# Aux_Power_Board_V2_1.net
KiCad netlist of a schematic drawn in EAGLE
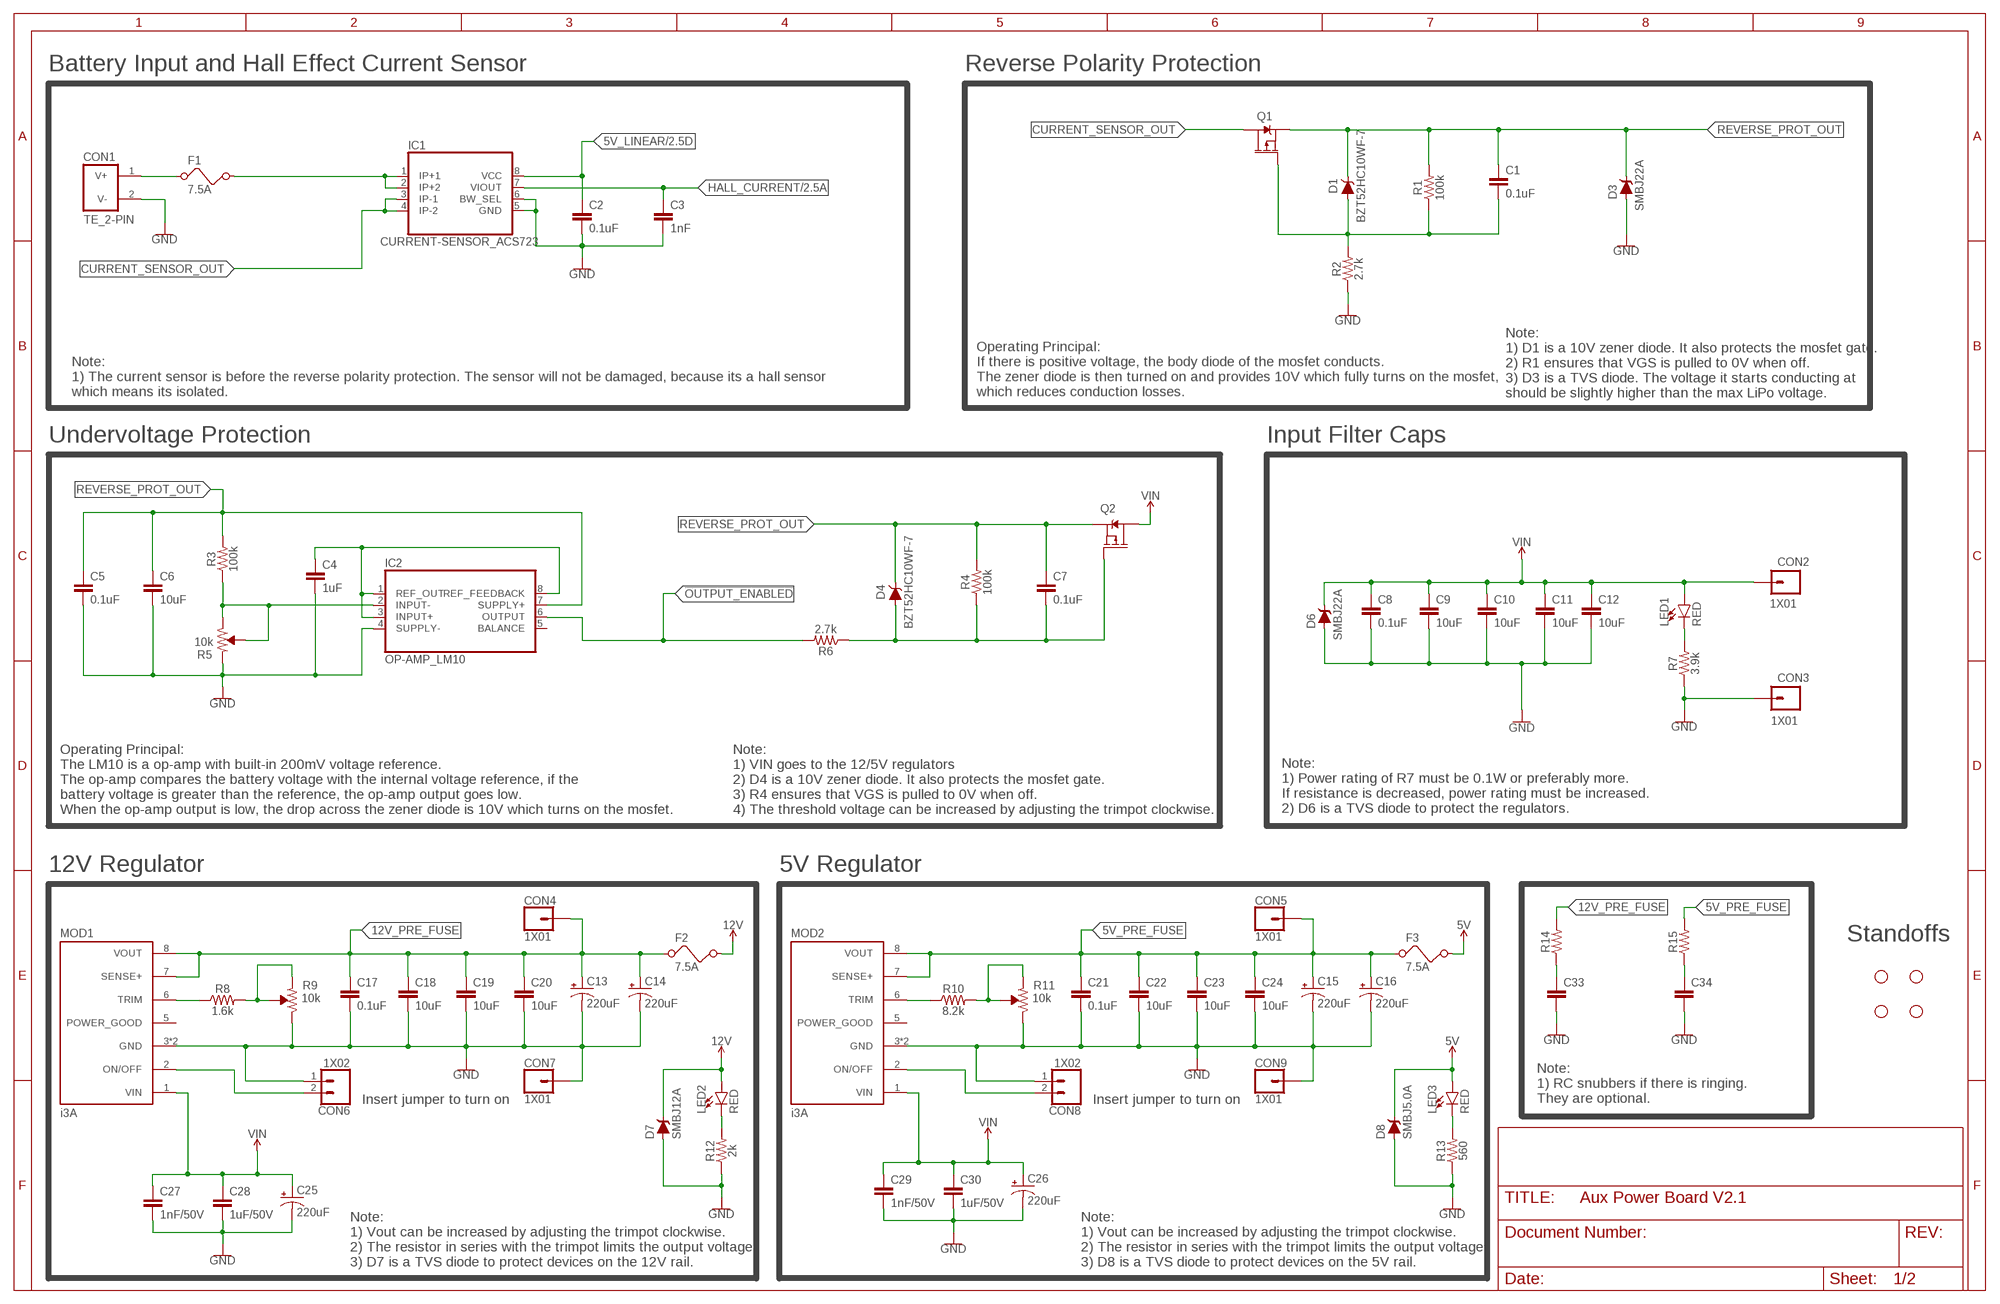
[diagram p0: schematic, sheet 1]
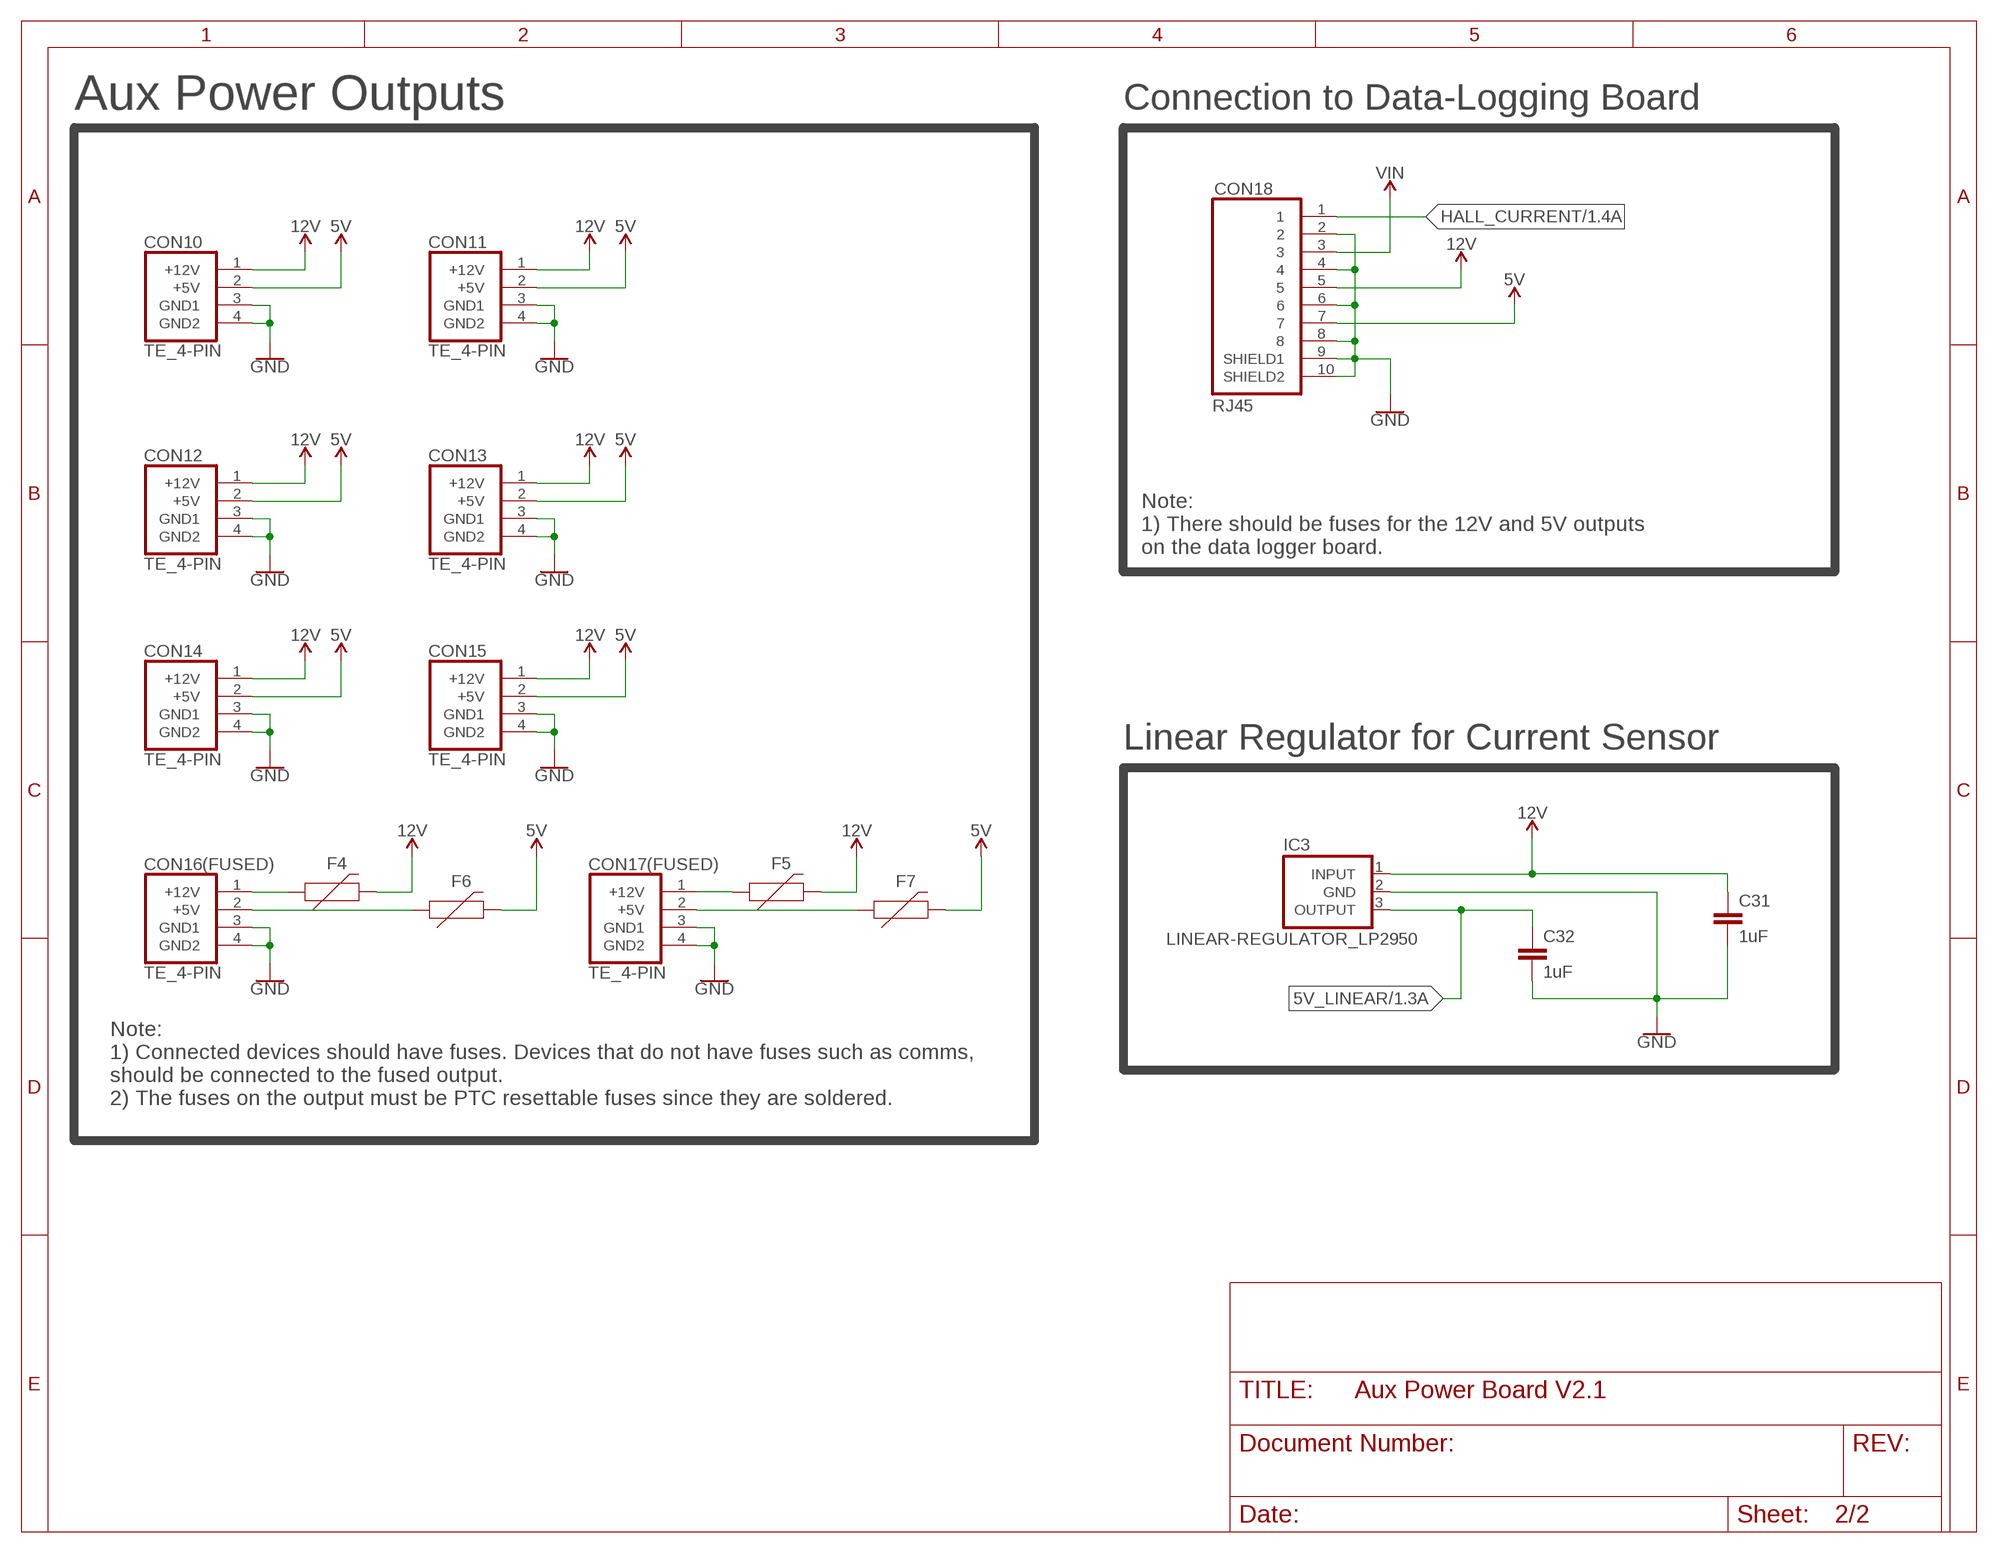
[diagram p1: schematic, sheet 2]

(export (version "E")
  (design (tool "Eeschema 10.0.6"))
  (components
    (comp (ref "C1")
      (value "0.1uF")
      (footprint "eagle-import:0805")
      (libsource (lib "eagle-import") (part "CAPACITOR_0805"))
    )
    (comp (ref "C2")
      (value "0.1uF")
      (footprint "eagle-import:0805")
      (libsource (lib "eagle-import") (part "CAPACITOR_0805"))
    )
    (comp (ref "C3")
      (value "1nF")
      (footprint "eagle-import:0805")
      (libsource (lib "eagle-import") (part "CAPACITOR_0805"))
    )
    (comp (ref "C4")
      (value "1uF")
      (footprint "eagle-import:0805")
      (libsource (lib "eagle-import") (part "CAPACITOR_0805"))
    )
    (comp (ref "C5")
      (value "0.1uF")
      (footprint "eagle-import:0805")
      (libsource (lib "eagle-import") (part "CAPACITOR_0805"))
    )
    (comp (ref "C6")
      (value "10uF")
      (footprint "eagle-import:1210")
      (libsource (lib "eagle-import") (part "CAPACITOR_1210"))
    )
    (comp (ref "C7")
      (value "0.1uF")
      (footprint "eagle-import:0805")
      (libsource (lib "eagle-import") (part "CAPACITOR_0805"))
    )
    (comp (ref "C8")
      (value "0.1uF")
      (footprint "eagle-import:0805")
      (libsource (lib "eagle-import") (part "CAPACITOR_0805"))
    )
    (comp (ref "C9")
      (value "10uF")
      (footprint "eagle-import:1210")
      (libsource (lib "eagle-import") (part "CAPACITOR_1210"))
    )
    (comp (ref "C10")
      (value "10uF")
      (footprint "eagle-import:1210")
      (libsource (lib "eagle-import") (part "CAPACITOR_1210"))
    )
    (comp (ref "C11")
      (value "10uF")
      (footprint "eagle-import:1210")
      (libsource (lib "eagle-import") (part "CAPACITOR_1210"))
    )
    (comp (ref "C12")
      (value "10uF")
      (footprint "eagle-import:1210")
      (libsource (lib "eagle-import") (part "CAPACITOR_1210"))
    )
    (comp (ref "C13")
      (value "220uF")
      (footprint "eagle-import:CAPACITOR_220UF_63V")
      (libsource (lib "eagle-import") (part "CAPACITOR_ELECTROLYTIC_220UF"))
    )
    (comp (ref "C14")
      (value "220uF")
      (footprint "eagle-import:CAPACITOR_220UF_63V")
      (libsource (lib "eagle-import") (part "CAPACITOR_ELECTROLYTIC_220UF"))
    )
    (comp (ref "C15")
      (value "220uF")
      (footprint "eagle-import:CAPACITOR_220UF_63V")
      (libsource (lib "eagle-import") (part "CAPACITOR_ELECTROLYTIC_220UF"))
    )
    (comp (ref "C16")
      (value "220uF")
      (footprint "eagle-import:CAPACITOR_220UF_63V")
      (libsource (lib "eagle-import") (part "CAPACITOR_ELECTROLYTIC_220UF"))
    )
    (comp (ref "C17")
      (value "0.1uF")
      (footprint "eagle-import:0805")
      (libsource (lib "eagle-import") (part "CAPACITOR_0805"))
    )
    (comp (ref "C18")
      (value "10uF")
      (footprint "eagle-import:0805")
      (libsource (lib "eagle-import") (part "CAPACITOR_0805"))
    )
    (comp (ref "C19")
      (value "10uF")
      (footprint "eagle-import:0805")
      (libsource (lib "eagle-import") (part "CAPACITOR_0805"))
    )
    (comp (ref "C20")
      (value "10uF")
      (footprint "eagle-import:0805")
      (libsource (lib "eagle-import") (part "CAPACITOR_0805"))
    )
    (comp (ref "C21")
      (value "0.1uF")
      (footprint "eagle-import:0805")
      (libsource (lib "eagle-import") (part "CAPACITOR_0805"))
    )
    (comp (ref "C22")
      (value "10uF")
      (footprint "eagle-import:0805")
      (libsource (lib "eagle-import") (part "CAPACITOR_0805"))
    )
    (comp (ref "C23")
      (value "10uF")
      (footprint "eagle-import:0805")
      (libsource (lib "eagle-import") (part "CAPACITOR_0805"))
    )
    (comp (ref "C24")
      (value "10uF")
      (footprint "eagle-import:0805")
      (libsource (lib "eagle-import") (part "CAPACITOR_0805"))
    )
    (comp (ref "C25")
      (value "220uF")
      (footprint "eagle-import:CAPACITOR_220UF_63V")
      (libsource (lib "eagle-import") (part "CAPACITOR_ELECTROLYTIC_220UF"))
    )
    (comp (ref "C26")
      (value "220uF")
      (footprint "eagle-import:CAPACITOR_220UF_63V")
      (libsource (lib "eagle-import") (part "CAPACITOR_ELECTROLYTIC_220UF"))
    )
    (comp (ref "C27")
      (value "1nF/50V")
      (footprint "eagle-import:0805")
      (libsource (lib "eagle-import") (part "CAPACITOR_0805"))
    )
    (comp (ref "C28")
      (value "1uF/50V")
      (footprint "eagle-import:0805")
      (libsource (lib "eagle-import") (part "CAPACITOR_0805"))
    )
    (comp (ref "C29")
      (value "1nF/50V")
      (footprint "eagle-import:0805")
      (libsource (lib "eagle-import") (part "CAPACITOR_0805"))
    )
    (comp (ref "C30")
      (value "1uF/50V")
      (footprint "eagle-import:0805")
      (libsource (lib "eagle-import") (part "CAPACITOR_0805"))
    )
    (comp (ref "C33")
      (value "CAPACITOR_0805")
      (footprint "eagle-import:0805")
      (libsource (lib "eagle-import") (part "CAPACITOR_0805"))
    )
    (comp (ref "C34")
      (value "CAPACITOR_0805")
      (footprint "eagle-import:0805")
      (libsource (lib "eagle-import") (part "CAPACITOR_0805"))
    )
    (comp (ref "CON1")
      (value "TE_2-PIN")
      (footprint "eagle-import:TE_2-PIN")
      (libsource (lib "eagle-import") (part "TE_2-PIN"))
    )
    (comp (ref "CON2")
      (value "1X01")
      (footprint "eagle-import:1X01")
      (libsource (lib "eagle-import") (part "1X01"))
    )
    (comp (ref "CON3")
      (value "1X01")
      (footprint "eagle-import:1X01")
      (libsource (lib "eagle-import") (part "1X01"))
    )
    (comp (ref "CON4")
      (value "1X01")
      (footprint "eagle-import:1X01")
      (libsource (lib "eagle-import") (part "1X01"))
    )
    (comp (ref "CON5")
      (value "1X01")
      (footprint "eagle-import:1X01")
      (libsource (lib "eagle-import") (part "1X01"))
    )
    (comp (ref "CON6")
      (value "1X02")
      (footprint "eagle-import:1X02")
      (libsource (lib "eagle-import") (part "1X02"))
    )
    (comp (ref "CON7")
      (value "1X01")
      (footprint "eagle-import:1X01")
      (libsource (lib "eagle-import") (part "1X01"))
    )
    (comp (ref "CON8")
      (value "1X02")
      (footprint "eagle-import:1X02")
      (libsource (lib "eagle-import") (part "1X02"))
    )
    (comp (ref "CON9")
      (value "1X01")
      (footprint "eagle-import:1X01")
      (libsource (lib "eagle-import") (part "1X01"))
    )
    (comp (ref "D1")
      (value "BZT52HC10WF-7")
      (footprint "eagle-import:SOD123FL")
      (libsource (lib "eagle-import") (part "DIODE_ZENER_SOD123F"))
    )
    (comp (ref "D3")
      (value "SMBJ22A")
      (footprint "eagle-import:DO214AA")
      (libsource (lib "eagle-import") (part "DIODE_TVS_UNI_DO-214AA"))
    )
    (comp (ref "D4")
      (value "BZT52HC10WF-7")
      (footprint "eagle-import:SOD123FL")
      (libsource (lib "eagle-import") (part "DIODE_ZENER_SOD123F"))
    )
    (comp (ref "D6")
      (value "SMBJ22A")
      (footprint "eagle-import:DO214AA")
      (libsource (lib "eagle-import") (part "DIODE_TVS_UNI_DO-214AA"))
    )
    (comp (ref "D7")
      (value "SMBJ12A")
      (footprint "eagle-import:DO214AA")
      (libsource (lib "eagle-import") (part "DIODE_TVS_UNI_DO-214AA"))
    )
    (comp (ref "D8")
      (value "SMBJ5.0A")
      (footprint "eagle-import:DO214AA")
      (libsource (lib "eagle-import") (part "DIODE_TVS_UNI_DO-214AA"))
    )
    (comp (ref "F1")
      (value "7.5A")
      (footprint "eagle-import:FUSEHOLDER_VERTICAL")
      (libsource (lib "eagle-import") (part "FUSEHOLDER_VERTICAL"))
    )
    (comp (ref "F2")
      (value "7.5A")
      (footprint "eagle-import:FUSEHOLDER_VERTICAL")
      (libsource (lib "eagle-import") (part "FUSEHOLDER_VERTICAL"))
    )
    (comp (ref "F3")
      (value "7.5A")
      (footprint "eagle-import:FUSEHOLDER_VERTICAL")
      (libsource (lib "eagle-import") (part "FUSEHOLDER_VERTICAL"))
    )
    (comp (ref "H1")
      (value "STAND-OFF")
      (footprint "eagle-import:STAND-OFF")
      (libsource (lib "eagle-import") (part "STAND-OFF"))
    )
    (comp (ref "H2")
      (value "STAND-OFF")
      (footprint "eagle-import:STAND-OFF")
      (libsource (lib "eagle-import") (part "STAND-OFF"))
    )
    (comp (ref "H3")
      (value "STAND-OFF")
      (footprint "eagle-import:STAND-OFF")
      (libsource (lib "eagle-import") (part "STAND-OFF"))
    )
    (comp (ref "H4")
      (value "STAND-OFF")
      (footprint "eagle-import:STAND-OFF")
      (libsource (lib "eagle-import") (part "STAND-OFF"))
    )
    (comp (ref "IC1")
      (value "CURRENT-SENSOR_ACS723")
      (footprint "eagle-import:SOIC8")
      (libsource (lib "eagle-import") (part "CURRENT-SENSOR_ACS723"))
    )
    (comp (ref "IC2")
      (value "OP-AMP_LM10")
      (footprint "eagle-import:DIP08")
      (libsource (lib "eagle-import") (part "OP-AMP_LM10"))
    )
    (comp (ref "LED1")
      (value "RED")
      (footprint "eagle-import:0805_LED")
      (libsource (lib "eagle-import") (part "LED_0805"))
    )
    (comp (ref "LED2")
      (value "RED")
      (footprint "eagle-import:0805_LED")
      (libsource (lib "eagle-import") (part "LED_0805"))
    )
    (comp (ref "LED3")
      (value "RED")
      (footprint "eagle-import:0805_LED")
      (libsource (lib "eagle-import") (part "LED_0805"))
    )
    (comp (ref "MOD1")
      (value "i3A")
      (footprint "eagle-import:CONVERTER_I3A")
      (libsource (lib "eagle-import") (part "CONVERTER_I3A"))
    )
    (comp (ref "MOD2")
      (value "i3A")
      (footprint "eagle-import:CONVERTER_I3A")
      (libsource (lib "eagle-import") (part "CONVERTER_I3A"))
    )
    (comp (ref "Q1")
      (value "MOSFET_PMOS_TO-263")
      (footprint "eagle-import:TO-263_D2PAK")
      (libsource (lib "eagle-import") (part "MOSFET_PMOS_TO-263"))
    )
    (comp (ref "Q2")
      (value "MOSFET_PMOS_TO-263")
      (footprint "eagle-import:TO-263_D2PAK")
      (libsource (lib "eagle-import") (part "MOSFET_PMOS_TO-263"))
    )
    (comp (ref "R1")
      (value "100k")
      (footprint "eagle-import:0805")
      (libsource (lib "eagle-import") (part "RESISTOR_0805"))
    )
    (comp (ref "R2")
      (value "2.7k")
      (footprint "eagle-import:0805")
      (libsource (lib "eagle-import") (part "RESISTOR_0805"))
    )
    (comp (ref "R3")
      (value "100k")
      (footprint "eagle-import:0805")
      (libsource (lib "eagle-import") (part "RESISTOR_0805"))
    )
    (comp (ref "R4")
      (value "100k")
      (footprint "eagle-import:0805")
      (libsource (lib "eagle-import") (part "RESISTOR_0805"))
    )
    (comp (ref "R5")
      (value "10k")
      (footprint "eagle-import:TRIMPOT")
      (libsource (lib "eagle-import") (part "RESISTOR_TRIMPOT"))
    )
    (comp (ref "R6")
      (value "2.7k")
      (footprint "eagle-import:0805")
      (libsource (lib "eagle-import") (part "RESISTOR_0805"))
    )
    (comp (ref "R7")
      (value "3.9k")
      (footprint "eagle-import:0805")
      (libsource (lib "eagle-import") (part "RESISTOR_0805"))
    )
    (comp (ref "R8")
      (value "1.6k")
      (footprint "eagle-import:0805")
      (libsource (lib "eagle-import") (part "RESISTOR_0805"))
    )
    (comp (ref "R9")
      (value "10k")
      (footprint "eagle-import:TRIMPOT")
      (libsource (lib "eagle-import") (part "RESISTOR_TRIMPOT"))
    )
    (comp (ref "R10")
      (value "8.2k")
      (footprint "eagle-import:0805")
      (libsource (lib "eagle-import") (part "RESISTOR_0805"))
    )
    (comp (ref "R11")
      (value "10k")
      (footprint "eagle-import:TRIMPOT")
      (libsource (lib "eagle-import") (part "RESISTOR_TRIMPOT"))
    )
    (comp (ref "R12")
      (value "2k")
      (footprint "eagle-import:0805")
      (libsource (lib "eagle-import") (part "RESISTOR_0805"))
    )
    (comp (ref "R13")
      (value "560")
      (footprint "eagle-import:0805")
      (libsource (lib "eagle-import") (part "RESISTOR_0805"))
    )
    (comp (ref "R14")
      (value "RESISTOR_0805")
      (footprint "eagle-import:0805")
      (libsource (lib "eagle-import") (part "RESISTOR_0805"))
    )
    (comp (ref "R15")
      (value "RESISTOR_0805")
      (footprint "eagle-import:0805")
      (libsource (lib "eagle-import") (part "RESISTOR_0805"))
    )
    (comp (ref "C31")
      (value "1uF")
      (footprint "eagle-import:0805")
      (libsource (lib "eagle-import") (part "CAPACITOR_0805"))
    )
    (comp (ref "C32")
      (value "1uF")
      (footprint "eagle-import:0805")
      (libsource (lib "eagle-import") (part "CAPACITOR_0805"))
    )
    (comp (ref "CON10")
      (value "TE_4-PIN")
      (footprint "eagle-import:TE_4-PIN")
      (libsource (lib "eagle-import") (part "TE_4-PIN"))
    )
    (comp (ref "CON11")
      (value "TE_4-PIN")
      (footprint "eagle-import:TE_4-PIN")
      (libsource (lib "eagle-import") (part "TE_4-PIN"))
    )
    (comp (ref "CON12")
      (value "TE_4-PIN")
      (footprint "eagle-import:TE_4-PIN")
      (libsource (lib "eagle-import") (part "TE_4-PIN"))
    )
    (comp (ref "CON13")
      (value "TE_4-PIN")
      (footprint "eagle-import:TE_4-PIN")
      (libsource (lib "eagle-import") (part "TE_4-PIN"))
    )
    (comp (ref "CON14")
      (value "TE_4-PIN")
      (footprint "eagle-import:TE_4-PIN")
      (libsource (lib "eagle-import") (part "TE_4-PIN"))
    )
    (comp (ref "CON15")
      (value "TE_4-PIN")
      (footprint "eagle-import:TE_4-PIN")
      (libsource (lib "eagle-import") (part "TE_4-PIN"))
    )
    (comp (ref "CON16(FUSED)")
      (value "TE_4-PIN")
      (footprint "eagle-import:TE_4-PIN")
      (libsource (lib "eagle-import") (part "TE_4-PIN"))
    )
    (comp (ref "CON17(FUSED)")
      (value "TE_4-PIN")
      (footprint "eagle-import:TE_4-PIN")
      (libsource (lib "eagle-import") (part "TE_4-PIN"))
    )
    (comp (ref "CON18")
      (value "RJ45")
      (footprint "eagle-import:RJ45")
      (libsource (lib "eagle-import") (part "RJ45"))
    )
    (comp (ref "F4")
      (value "FUSE_1210_RESETTABLE")
      (footprint "eagle-import:1210")
      (libsource (lib "eagle-import") (part "FUSE_1210_RESETTABLE"))
    )
    (comp (ref "F5")
      (value "FUSE_1210_RESETTABLE")
      (footprint "eagle-import:1210")
      (libsource (lib "eagle-import") (part "FUSE_1210_RESETTABLE"))
    )
    (comp (ref "F6")
      (value "FUSE_1210_RESETTABLE")
      (footprint "eagle-import:1210")
      (libsource (lib "eagle-import") (part "FUSE_1210_RESETTABLE"))
    )
    (comp (ref "F7")
      (value "FUSE_1210_RESETTABLE")
      (footprint "eagle-import:1210")
      (libsource (lib "eagle-import") (part "FUSE_1210_RESETTABLE"))
    )
    (comp (ref "IC3")
      (value "LINEAR-REGULATOR_LP2950")
      (footprint "eagle-import:TO92")
      (libsource (lib "eagle-import") (part "LINEAR-REGULATOR_LP2950"))
    )
  )
  (nets
    (net (code "1") (name "5V") (class "Default")
      (node (ref "CON10") (pin "2") (pinfunction "+5V_2") (pintype "passive"))
      (node (ref "CON11") (pin "2") (pinfunction "+5V_2") (pintype "passive"))
      (node (ref "CON12") (pin "2") (pinfunction "+5V_2") (pintype "passive"))
      (node (ref "CON13") (pin "2") (pinfunction "+5V_2") (pintype "passive"))
      (node (ref "CON14") (pin "2") (pinfunction "+5V_2") (pintype "passive"))
      (node (ref "CON15") (pin "2") (pinfunction "+5V_2") (pintype "passive"))
      (node (ref "CON18") (pin "7") (pinfunction "7_7") (pintype "passive"))
      (node (ref "D8") (pin "C") (pinfunction "C_C") (pintype "passive"))
      (node (ref "F3") (pin "3") (pinfunction "2_3") (pintype "passive"))
      (node (ref "F3") (pin "4") (pinfunction "2_4") (pintype "passive"))
      (node (ref "F6") (pin "2") (pinfunction "2_2") (pintype "bidirectional"))
      (node (ref "F7") (pin "2") (pinfunction "2_2") (pintype "bidirectional"))
      (node (ref "LED3") (pin "1") (pinfunction "A_1") (pintype "passive"))
    )
    (net (code "2") (name "5V_LINEAR") (class "Default")
      (node (ref "C2") (pin "1") (pinfunction "1_1") (pintype "passive"))
      (node (ref "C32") (pin "1") (pinfunction "1_1") (pintype "passive"))
      (node (ref "IC1") (pin "8") (pinfunction "VCC_8") (pintype "bidirectional"))
      (node (ref "IC3") (pin "3") (pinfunction "OUTPUT_3") (pintype "bidirectional"))
    )
    (net (code "3") (name "5V_PRE_FUSE") (class "Default")
      (node (ref "C15") (pin "+") (pinfunction "+_+") (pintype "passive"))
      (node (ref "C16") (pin "+") (pinfunction "+_+") (pintype "passive"))
      (node (ref "C21") (pin "1") (pinfunction "1_1") (pintype "passive"))
      (node (ref "C22") (pin "1") (pinfunction "1_1") (pintype "passive"))
      (node (ref "C23") (pin "1") (pinfunction "1_1") (pintype "passive"))
      (node (ref "C24") (pin "1") (pinfunction "1_1") (pintype "passive"))
      (node (ref "CON5") (pin "1") (pinfunction "1_1") (pintype "passive"))
      (node (ref "F3") (pin "1") (pinfunction "1_1") (pintype "passive"))
      (node (ref "F3") (pin "2") (pinfunction "1_2") (pintype "passive"))
      (node (ref "MOD2") (pin "7") (pinfunction "SENSE+_7") (pintype "bidirectional"))
      (node (ref "MOD2") (pin "8") (pinfunction "VOUT_8") (pintype "bidirectional"))
      (node (ref "R15") (pin "2") (pinfunction "2_2") (pintype "passive"))
    )
    (net (code "4") (name "12V") (class "Default")
      (node (ref "C31") (pin "1") (pinfunction "1_1") (pintype "passive"))
      (node (ref "CON10") (pin "1") (pinfunction "+12V_1") (pintype "passive"))
      (node (ref "CON11") (pin "1") (pinfunction "+12V_1") (pintype "passive"))
      (node (ref "CON12") (pin "1") (pinfunction "+12V_1") (pintype "passive"))
      (node (ref "CON13") (pin "1") (pinfunction "+12V_1") (pintype "passive"))
      (node (ref "CON14") (pin "1") (pinfunction "+12V_1") (pintype "passive"))
      (node (ref "CON15") (pin "1") (pinfunction "+12V_1") (pintype "passive"))
      (node (ref "CON18") (pin "5") (pinfunction "5_5") (pintype "passive"))
      (node (ref "D7") (pin "C") (pinfunction "C_C") (pintype "passive"))
      (node (ref "F2") (pin "3") (pinfunction "2_3") (pintype "passive"))
      (node (ref "F2") (pin "4") (pinfunction "2_4") (pintype "passive"))
      (node (ref "F4") (pin "2") (pinfunction "2_2") (pintype "bidirectional"))
      (node (ref "F5") (pin "2") (pinfunction "2_2") (pintype "bidirectional"))
      (node (ref "IC3") (pin "1") (pinfunction "INPUT_1") (pintype "bidirectional"))
      (node (ref "LED2") (pin "1") (pinfunction "A_1") (pintype "passive"))
    )
    (net (code "5") (name "12V_PRE_FUSE") (class "Default")
      (node (ref "C13") (pin "+") (pinfunction "+_+") (pintype "passive"))
      (node (ref "C14") (pin "+") (pinfunction "+_+") (pintype "passive"))
      (node (ref "C17") (pin "1") (pinfunction "1_1") (pintype "passive"))
      (node (ref "C18") (pin "1") (pinfunction "1_1") (pintype "passive"))
      (node (ref "C19") (pin "1") (pinfunction "1_1") (pintype "passive"))
      (node (ref "C20") (pin "1") (pinfunction "1_1") (pintype "passive"))
      (node (ref "CON4") (pin "1") (pinfunction "1_1") (pintype "passive"))
      (node (ref "F2") (pin "1") (pinfunction "1_1") (pintype "passive"))
      (node (ref "F2") (pin "2") (pinfunction "1_2") (pintype "passive"))
      (node (ref "MOD1") (pin "7") (pinfunction "SENSE+_7") (pintype "bidirectional"))
      (node (ref "MOD1") (pin "8") (pinfunction "VOUT_8") (pintype "bidirectional"))
      (node (ref "R14") (pin "2") (pinfunction "2_2") (pintype "passive"))
    )
    (net (code "6") (name "CURRENT_SENSOR_OUT") (class "Default")
      (node (ref "IC1") (pin "3") (pinfunction "IP-1_3") (pintype "bidirectional"))
      (node (ref "IC1") (pin "4") (pinfunction "IP-2_4") (pintype "bidirectional"))
      (node (ref "Q1") (pin "2") (pinfunction "D_2") (pintype "bidirectional"))
    )
    (net (code "7") (name "GND") (class "Default")
      (node (ref "C10") (pin "2") (pinfunction "2_2") (pintype "passive"))
      (node (ref "C11") (pin "2") (pinfunction "2_2") (pintype "passive"))
      (node (ref "C12") (pin "2") (pinfunction "2_2") (pintype "passive"))
      (node (ref "C13") (pin "-") (pinfunction "-_-") (pintype "passive"))
      (node (ref "C14") (pin "-") (pinfunction "-_-") (pintype "passive"))
      (node (ref "C15") (pin "-") (pinfunction "-_-") (pintype "passive"))
      (node (ref "C16") (pin "-") (pinfunction "-_-") (pintype "passive"))
      (node (ref "C17") (pin "2") (pinfunction "2_2") (pintype "passive"))
      (node (ref "C18") (pin "2") (pinfunction "2_2") (pintype "passive"))
      (node (ref "C19") (pin "2") (pinfunction "2_2") (pintype "passive"))
      (node (ref "C2") (pin "2") (pinfunction "2_2") (pintype "passive"))
      (node (ref "C20") (pin "2") (pinfunction "2_2") (pintype "passive"))
      (node (ref "C21") (pin "2") (pinfunction "2_2") (pintype "passive"))
      (node (ref "C22") (pin "2") (pinfunction "2_2") (pintype "passive"))
      (node (ref "C23") (pin "2") (pinfunction "2_2") (pintype "passive"))
      (node (ref "C24") (pin "2") (pinfunction "2_2") (pintype "passive"))
      (node (ref "C25") (pin "-") (pinfunction "-_-") (pintype "passive"))
      (node (ref "C26") (pin "-") (pinfunction "-_-") (pintype "passive"))
      (node (ref "C27") (pin "2") (pinfunction "2_2") (pintype "passive"))
      (node (ref "C28") (pin "2") (pinfunction "2_2") (pintype "passive"))
      (node (ref "C29") (pin "2") (pinfunction "2_2") (pintype "passive"))
      (node (ref "C3") (pin "2") (pinfunction "2_2") (pintype "passive"))
      (node (ref "C30") (pin "2") (pinfunction "2_2") (pintype "passive"))
      (node (ref "C31") (pin "2") (pinfunction "2_2") (pintype "passive"))
      (node (ref "C32") (pin "2") (pinfunction "2_2") (pintype "passive"))
      (node (ref "C33") (pin "2") (pinfunction "2_2") (pintype "passive"))
      (node (ref "C34") (pin "2") (pinfunction "2_2") (pintype "passive"))
      (node (ref "C4") (pin "2") (pinfunction "2_2") (pintype "passive"))
      (node (ref "C5") (pin "2") (pinfunction "2_2") (pintype "passive"))
      (node (ref "C6") (pin "2") (pinfunction "2_2") (pintype "passive"))
      (node (ref "C8") (pin "2") (pinfunction "2_2") (pintype "passive"))
      (node (ref "C9") (pin "2") (pinfunction "2_2") (pintype "passive"))
      (node (ref "CON1") (pin "2") (pinfunction "V-_2") (pintype "passive"))
      (node (ref "CON10") (pin "3") (pinfunction "GND1_3") (pintype "passive"))
      (node (ref "CON10") (pin "4") (pinfunction "GND2_4") (pintype "passive"))
      (node (ref "CON11") (pin "3") (pinfunction "GND1_3") (pintype "passive"))
      (node (ref "CON11") (pin "4") (pinfunction "GND2_4") (pintype "passive"))
      (node (ref "CON12") (pin "3") (pinfunction "GND1_3") (pintype "passive"))
      (node (ref "CON12") (pin "4") (pinfunction "GND2_4") (pintype "passive"))
      (node (ref "CON13") (pin "3") (pinfunction "GND1_3") (pintype "passive"))
      (node (ref "CON13") (pin "4") (pinfunction "GND2_4") (pintype "passive"))
      (node (ref "CON14") (pin "3") (pinfunction "GND1_3") (pintype "passive"))
      (node (ref "CON14") (pin "4") (pinfunction "GND2_4") (pintype "passive"))
      (node (ref "CON15") (pin "3") (pinfunction "GND1_3") (pintype "passive"))
      (node (ref "CON15") (pin "4") (pinfunction "GND2_4") (pintype "passive"))
      (node (ref "CON16(FUSED)") (pin "3") (pinfunction "GND1_3") (pintype "passive"))
      (node (ref "CON16(FUSED)") (pin "4") (pinfunction "GND2_4") (pintype "passive"))
      (node (ref "CON17(FUSED)") (pin "3") (pinfunction "GND1_3") (pintype "passive"))
      (node (ref "CON17(FUSED)") (pin "4") (pinfunction "GND2_4") (pintype "passive"))
      (node (ref "CON18") (pin "10") (pinfunction "SHIELD2_10") (pintype "passive"))
      (node (ref "CON18") (pin "2") (pinfunction "2_2") (pintype "passive"))
      (node (ref "CON18") (pin "4") (pinfunction "4_4") (pintype "passive"))
      (node (ref "CON18") (pin "6") (pinfunction "6_6") (pintype "passive"))
      (node (ref "CON18") (pin "8") (pinfunction "8_8") (pintype "passive"))
      (node (ref "CON18") (pin "9") (pinfunction "SHIELD1_9") (pintype "passive"))
      (node (ref "CON3") (pin "1") (pinfunction "1_1") (pintype "passive"))
      (node (ref "CON6") (pin "1") (pinfunction "1_1") (pintype "passive"))
      (node (ref "CON7") (pin "1") (pinfunction "1_1") (pintype "passive"))
      (node (ref "CON8") (pin "1") (pinfunction "1_1") (pintype "passive"))
      (node (ref "CON9") (pin "1") (pinfunction "1_1") (pintype "passive"))
      (node (ref "D3") (pin "A") (pinfunction "A_A") (pintype "passive"))
      (node (ref "D6") (pin "A") (pinfunction "A_A") (pintype "passive"))
      (node (ref "D7") (pin "A") (pinfunction "A_A") (pintype "passive"))
      (node (ref "D8") (pin "A") (pinfunction "A_A") (pintype "passive"))
      (node (ref "IC1") (pin "5") (pinfunction "GND_5") (pintype "bidirectional"))
      (node (ref "IC1") (pin "6") (pinfunction "BW_SEL_6") (pintype "bidirectional"))
      (node (ref "IC2") (pin "4") (pinfunction "SUPPLY-_4") (pintype "bidirectional"))
      (node (ref "IC3") (pin "2") (pinfunction "GND_2") (pintype "bidirectional"))
      (node (ref "MOD1") (pin "3") (pinfunction "GND_3") (pintype "bidirectional"))
      (node (ref "MOD1") (pin "4") (pinfunction "GND_4") (pintype "bidirectional"))
      (node (ref "MOD2") (pin "3") (pinfunction "GND_3") (pintype "bidirectional"))
      (node (ref "MOD2") (pin "4") (pinfunction "GND_4") (pintype "bidirectional"))
      (node (ref "R11") (pin "3") (pinfunction "CW_3") (pintype "passive"))
      (node (ref "R12") (pin "1") (pinfunction "1_1") (pintype "passive"))
      (node (ref "R13") (pin "1") (pinfunction "1_1") (pintype "passive"))
      (node (ref "R2") (pin "1") (pinfunction "1_1") (pintype "passive"))
      (node (ref "R5") (pin "1") (pinfunction "CCW_1") (pintype "passive"))
      (node (ref "R7") (pin "1") (pinfunction "1_1") (pintype "passive"))
      (node (ref "R9") (pin "3") (pinfunction "CW_3") (pintype "passive"))
    )
    (net (code "8") (name "HALL_CURRENT") (class "Default")
      (node (ref "C3") (pin "1") (pinfunction "1_1") (pintype "passive"))
      (node (ref "CON18") (pin "1") (pinfunction "1_1") (pintype "passive"))
      (node (ref "IC1") (pin "7") (pinfunction "VIOUT_7") (pintype "bidirectional"))
    )
    (net (code "9") (name "Net-(C33-Pad1)") (class "Default")
      (node (ref "C33") (pin "1") (pinfunction "1_1") (pintype "passive"))
      (node (ref "R14") (pin "1") (pinfunction "1_1") (pintype "passive"))
    )
    (net (code "10") (name "Net-(C34-Pad1)") (class "Default")
      (node (ref "C34") (pin "1") (pinfunction "1_1") (pintype "passive"))
      (node (ref "R15") (pin "1") (pinfunction "1_1") (pintype "passive"))
    )
    (net (code "11") (name "Net-(CON1-V+)") (class "Default")
      (node (ref "CON1") (pin "1") (pinfunction "V+_1") (pintype "passive"))
      (node (ref "F1") (pin "1") (pinfunction "1_1") (pintype "passive"))
      (node (ref "F1") (pin "2") (pinfunction "1_2") (pintype "passive"))
    )
    (net (code "12") (name "Net-(CON16(FUSED)-+5V)") (class "Default")
      (node (ref "CON16(FUSED)") (pin "2") (pinfunction "+5V_2") (pintype "passive"))
      (node (ref "F6") (pin "1") (pinfunction "1_1") (pintype "bidirectional"))
    )
    (net (code "13") (name "Net-(CON16(FUSED)-+12V)") (class "Default")
      (node (ref "CON16(FUSED)") (pin "1") (pinfunction "+12V_1") (pintype "passive"))
      (node (ref "F4") (pin "1") (pinfunction "1_1") (pintype "bidirectional"))
    )
    (net (code "14") (name "Net-(CON17(FUSED)-+5V)") (class "Default")
      (node (ref "CON17(FUSED)") (pin "2") (pinfunction "+5V_2") (pintype "passive"))
      (node (ref "F7") (pin "1") (pinfunction "1_1") (pintype "bidirectional"))
    )
    (net (code "15") (name "Net-(CON17(FUSED)-+12V)") (class "Default")
      (node (ref "CON17(FUSED)") (pin "1") (pinfunction "+12V_1") (pintype "passive"))
      (node (ref "F5") (pin "1") (pinfunction "1_1") (pintype "bidirectional"))
    )
    (net (code "16") (name "Net-(IC1-IP+1)") (class "Default")
      (node (ref "F1") (pin "3") (pinfunction "2_3") (pintype "passive"))
      (node (ref "F1") (pin "4") (pinfunction "2_4") (pintype "passive"))
      (node (ref "IC1") (pin "1") (pinfunction "IP+1_1") (pintype "bidirectional"))
      (node (ref "IC1") (pin "2") (pinfunction "IP+2_2") (pintype "bidirectional"))
    )
    (net (code "17") (name "Net-(IC2-INPUT+)") (class "Default")
      (node (ref "C4") (pin "1") (pinfunction "1_1") (pintype "passive"))
      (node (ref "IC2") (pin "1") (pinfunction "REF_OUT_1") (pintype "bidirectional"))
      (node (ref "IC2") (pin "3") (pinfunction "INPUT+_3") (pintype "bidirectional"))
      (node (ref "IC2") (pin "8") (pinfunction "REF_FEEDBACK_8") (pintype "bidirectional"))
    )
    (net (code "18") (name "Net-(IC2-INPUT-)") (class "Default")
      (node (ref "IC2") (pin "2") (pinfunction "INPUT-_2") (pintype "bidirectional"))
      (node (ref "R3") (pin "1") (pinfunction "1_1") (pintype "passive"))
      (node (ref "R5") (pin "2") (pinfunction "WIPER_2") (pintype "passive"))
      (node (ref "R5") (pin "3") (pinfunction "CW_3") (pintype "passive"))
    )
    (net (code "19") (name "Net-(LED1-C)") (class "Default")
      (node (ref "LED1") (pin "2") (pinfunction "C_2") (pintype "passive"))
      (node (ref "R7") (pin "2") (pinfunction "2_2") (pintype "passive"))
    )
    (net (code "20") (name "Net-(LED2-C)") (class "Default")
      (node (ref "LED2") (pin "2") (pinfunction "C_2") (pintype "passive"))
      (node (ref "R12") (pin "2") (pinfunction "2_2") (pintype "passive"))
    )
    (net (code "21") (name "Net-(LED3-C)") (class "Default")
      (node (ref "LED3") (pin "2") (pinfunction "C_2") (pintype "passive"))
      (node (ref "R13") (pin "2") (pinfunction "2_2") (pintype "passive"))
    )
    (net (code "22") (name "Net-(MOD1-ON{slash}OFF)") (class "Default")
      (node (ref "CON6") (pin "2") (pinfunction "2_2") (pintype "passive"))
      (node (ref "MOD1") (pin "2") (pinfunction "ON/OFF_2") (pintype "bidirectional"))
    )
    (net (code "23") (name "Net-(MOD1-TRIM)") (class "Default")
      (node (ref "MOD1") (pin "6") (pinfunction "TRIM_6") (pintype "bidirectional"))
      (node (ref "R8") (pin "1") (pinfunction "1_1") (pintype "passive"))
    )
    (net (code "24") (name "Net-(MOD2-ON{slash}OFF)") (class "Default")
      (node (ref "CON8") (pin "2") (pinfunction "2_2") (pintype "passive"))
      (node (ref "MOD2") (pin "2") (pinfunction "ON/OFF_2") (pintype "bidirectional"))
    )
    (net (code "25") (name "Net-(MOD2-TRIM)") (class "Default")
      (node (ref "MOD2") (pin "6") (pinfunction "TRIM_6") (pintype "bidirectional"))
      (node (ref "R10") (pin "1") (pinfunction "1_1") (pintype "passive"))
    )
    (net (code "26") (name "Net-(Q1-G)") (class "Default")
      (node (ref "C1") (pin "2") (pinfunction "2_2") (pintype "passive"))
      (node (ref "D1") (pin "A") (pinfunction "A_A") (pintype "passive"))
      (node (ref "Q1") (pin "1") (pinfunction "G_1") (pintype "bidirectional"))
      (node (ref "R1") (pin "1") (pinfunction "1_1") (pintype "passive"))
      (node (ref "R2") (pin "2") (pinfunction "2_2") (pintype "passive"))
    )
    (net (code "27") (name "Net-(Q2-G)") (class "Default")
      (node (ref "C7") (pin "2") (pinfunction "2_2") (pintype "passive"))
      (node (ref "D4") (pin "A") (pinfunction "A_A") (pintype "passive"))
      (node (ref "Q2") (pin "1") (pinfunction "G_1") (pintype "bidirectional"))
      (node (ref "R4") (pin "1") (pinfunction "1_1") (pintype "passive"))
      (node (ref "R6") (pin "1") (pinfunction "1_1") (pintype "passive"))
    )
    (net (code "28") (name "Net-(R9-CCW)") (class "Default")
      (node (ref "R8") (pin "2") (pinfunction "2_2") (pintype "passive"))
      (node (ref "R9") (pin "1") (pinfunction "CCW_1") (pintype "passive"))
      (node (ref "R9") (pin "2") (pinfunction "WIPER_2") (pintype "passive"))
    )
    (net (code "29") (name "Net-(R11-CCW)") (class "Default")
      (node (ref "R10") (pin "2") (pinfunction "2_2") (pintype "passive"))
      (node (ref "R11") (pin "1") (pinfunction "CCW_1") (pintype "passive"))
      (node (ref "R11") (pin "2") (pinfunction "WIPER_2") (pintype "passive"))
    )
    (net (code "30") (name "REVERSE_PROT_OUT") (class "Default")
      (node (ref "C1") (pin "1") (pinfunction "1_1") (pintype "passive"))
      (node (ref "C5") (pin "1") (pinfunction "1_1") (pintype "passive"))
      (node (ref "C6") (pin "1") (pinfunction "1_1") (pintype "passive"))
      (node (ref "C7") (pin "1") (pinfunction "1_1") (pintype "passive"))
      (node (ref "D1") (pin "C") (pinfunction "C_C") (pintype "passive"))
      (node (ref "D3") (pin "C") (pinfunction "C_C") (pintype "passive"))
      (node (ref "D4") (pin "C") (pinfunction "C_C") (pintype "passive"))
      (node (ref "IC2") (pin "7") (pinfunction "SUPPLY+_7") (pintype "bidirectional"))
      (node (ref "Q1") (pin "3") (pinfunction "S_3") (pintype "bidirectional"))
      (node (ref "Q2") (pin "3") (pinfunction "S_3") (pintype "bidirectional"))
      (node (ref "R1") (pin "2") (pinfunction "2_2") (pintype "passive"))
      (node (ref "R3") (pin "2") (pinfunction "2_2") (pintype "passive"))
      (node (ref "R4") (pin "2") (pinfunction "2_2") (pintype "passive"))
    )
    (net (code "31") (name "VIN") (class "Default")
      (node (ref "C10") (pin "1") (pinfunction "1_1") (pintype "passive"))
      (node (ref "C11") (pin "1") (pinfunction "1_1") (pintype "passive"))
      (node (ref "C12") (pin "1") (pinfunction "1_1") (pintype "passive"))
      (node (ref "C25") (pin "+") (pinfunction "+_+") (pintype "passive"))
      (node (ref "C26") (pin "+") (pinfunction "+_+") (pintype "passive"))
      (node (ref "C27") (pin "1") (pinfunction "1_1") (pintype "passive"))
      (node (ref "C28") (pin "1") (pinfunction "1_1") (pintype "passive"))
      (node (ref "C29") (pin "1") (pinfunction "1_1") (pintype "passive"))
      (node (ref "C30") (pin "1") (pinfunction "1_1") (pintype "passive"))
      (node (ref "C8") (pin "1") (pinfunction "1_1") (pintype "passive"))
      (node (ref "C9") (pin "1") (pinfunction "1_1") (pintype "passive"))
      (node (ref "CON18") (pin "3") (pinfunction "3_3") (pintype "passive"))
      (node (ref "CON2") (pin "1") (pinfunction "1_1") (pintype "passive"))
      (node (ref "D6") (pin "C") (pinfunction "C_C") (pintype "passive"))
      (node (ref "LED1") (pin "1") (pinfunction "A_1") (pintype "passive"))
      (node (ref "MOD1") (pin "1") (pinfunction "VIN_1") (pintype "bidirectional"))
      (node (ref "MOD2") (pin "1") (pinfunction "VIN_1") (pintype "bidirectional"))
      (node (ref "Q2") (pin "2") (pinfunction "D_2") (pintype "bidirectional"))
    )
    (net (code "32") (name "unconnected-(IC2-BALANCE-Pad5)") (class "Default")
      (node (ref "IC2") (pin "5") (pinfunction "BALANCE_5") (pintype "bidirectional"))
    )
    (net (code "33") (name "unconnected-(MOD1-POWER_GOOD-Pad5)") (class "Default")
      (node (ref "MOD1") (pin "5") (pinfunction "POWER_GOOD_5") (pintype "bidirectional"))
    )
    (net (code "34") (name "unconnected-(MOD2-POWER_GOOD-Pad5)") (class "Default")
      (node (ref "MOD2") (pin "5") (pinfunction "POWER_GOOD_5") (pintype "bidirectional"))
    )
    (net (code "35") (name "~{OUTPUT_ENABLED}") (class "Default")
      (node (ref "IC2") (pin "6") (pinfunction "OUTPUT_6") (pintype "bidirectional"))
      (node (ref "R6") (pin "2") (pinfunction "2_2") (pintype "passive"))
    )
  )
)
